# treiber.net
KiCad netlist of a schematic drawn in EAGLE
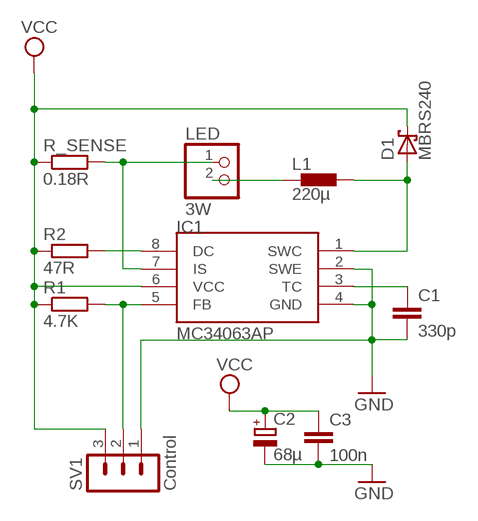
[diagram p0: schematic, sheet 1]

(export (version "E")
  (design (tool "Eeschema 10.0.6"))
  (components
    (comp (ref "C1")
      (value "330p")
      (footprint "eagle-import:C075-032X103")
      (libsource (lib "eagle-import") (part "C-EU075-032X103"))
    )
    (comp (ref "C2")
      (value "68µ")
      (footprint "eagle-import:E2,5-5")
      (libsource (lib "eagle-import") (part "CPOL-EUE2.5-5"))
    )
    (comp (ref "C3")
      (value "100n")
      (footprint "eagle-import:C5B2.5")
      (libsource (lib "eagle-import") (part "C5/2.5"))
    )
    (comp (ref "D1")
      (value "MBRS240")
      (footprint "eagle-import:DO35-7")
      (libsource (lib "eagle-import") (part "SCHOTTKY-DIODEDO35-7"))
    )
    (comp (ref "IC1")
      (value "MC34063AP")
      (footprint "eagle-import:DIL08")
      (libsource (lib "eagle-import") (part "MC34063AP"))
    )
    (comp (ref "L1")
      (value "220µ")
      (footprint "eagle-import:DR1030")
      (libsource (lib "eagle-import") (part "DR1030"))
    )
    (comp (ref "LED")
      (value "3W")
      (footprint "eagle-import:1X02")
      (libsource (lib "eagle-import") (part "PINHD-1X2"))
    )
    (comp (ref "R1")
      (value "4.7K")
      (footprint "eagle-import:0207_10")
      (libsource (lib "eagle-import") (part "R-EU_0207/10"))
    )
    (comp (ref "R2")
      (value "47R")
      (footprint "eagle-import:0207_10")
      (libsource (lib "eagle-import") (part "R-EU_0207/10"))
    )
    (comp (ref "R_SENSE")
      (value "0.18R")
      (footprint "eagle-import:0207_10")
      (libsource (lib "eagle-import") (part "R-EU_0207/10"))
    )
    (comp (ref "SV1")
      (value "Control")
      (footprint "eagle-import:MA03-1")
      (libsource (lib "eagle-import") (part "MA03-1"))
    )
  )
  (nets
    (net (code "1") (name "GND") (class "Default")
      (node (ref "C1") (pin "2") (pinfunction "2_2") (pintype "passive"))
      (node (ref "C2") (pin "-") (pinfunction "-_-") (pintype "passive"))
      (node (ref "C3") (pin "2") (pinfunction "2_2") (pintype "passive"))
      (node (ref "IC1") (pin "2") (pinfunction "SWE_2") (pintype "passive"))
      (node (ref "IC1") (pin "4") (pinfunction "GND_4") (pintype "passive"))
      (node (ref "SV1") (pin "1") (pinfunction "1_1") (pintype "passive"))
    )
    (net (code "2") (name "Net-(IC1-DC)") (class "Default")
      (node (ref "IC1") (pin "8") (pinfunction "DC_8") (pintype "passive"))
      (node (ref "R2") (pin "2") (pinfunction "2_2") (pintype "passive"))
    )
    (net (code "3") (name "Net-(IC1-FB)") (class "Default")
      (node (ref "IC1") (pin "5") (pinfunction "FB_5") (pintype "passive"))
      (node (ref "R1") (pin "2") (pinfunction "2_2") (pintype "passive"))
      (node (ref "SV1") (pin "2") (pinfunction "2_2") (pintype "passive"))
    )
    (net (code "4") (name "Net-(IC1-IS)") (class "Default")
      (node (ref "IC1") (pin "7") (pinfunction "IS_7") (pintype "passive"))
      (node (ref "LED") (pin "1") (pinfunction "1_1") (pintype "passive"))
      (node (ref "R_SENSE") (pin "2") (pinfunction "2_2") (pintype "passive"))
    )
    (net (code "5") (name "Net-(IC1-SWC)") (class "Default")
      (node (ref "D1") (pin "A") (pinfunction "A_A") (pintype "passive"))
      (node (ref "IC1") (pin "1") (pinfunction "SWC_1") (pintype "passive"))
      (node (ref "L1") (pin "2") (pinfunction "2_2") (pintype "passive"))
    )
    (net (code "6") (name "Net-(IC1-TC)") (class "Default")
      (node (ref "C1") (pin "1") (pinfunction "1_1") (pintype "passive"))
      (node (ref "IC1") (pin "3") (pinfunction "TC_3") (pintype "passive"))
    )
    (net (code "7") (name "Net-(L1-Pad1)") (class "Default")
      (node (ref "L1") (pin "1") (pinfunction "1_1") (pintype "passive"))
      (node (ref "LED") (pin "2") (pinfunction "2_2") (pintype "passive"))
    )
    (net (code "8") (name "VCC") (class "Default")
      (node (ref "C2") (pin "+") (pinfunction "+_+") (pintype "passive"))
      (node (ref "C3") (pin "1") (pinfunction "1_1") (pintype "passive"))
      (node (ref "D1") (pin "C") (pinfunction "C_C") (pintype "passive"))
      (node (ref "IC1") (pin "6") (pinfunction "VCC_6") (pintype "passive"))
      (node (ref "R1") (pin "1") (pinfunction "1_1") (pintype "passive"))
      (node (ref "R2") (pin "1") (pinfunction "1_1") (pintype "passive"))
      (node (ref "R_SENSE") (pin "1") (pinfunction "1_1") (pintype "passive"))
      (node (ref "SV1") (pin "3") (pinfunction "3_3") (pintype "passive"))
    )
  )
)
